# esp8266-lab-kit.net
KiCad netlist of a schematic drawn in EAGLE
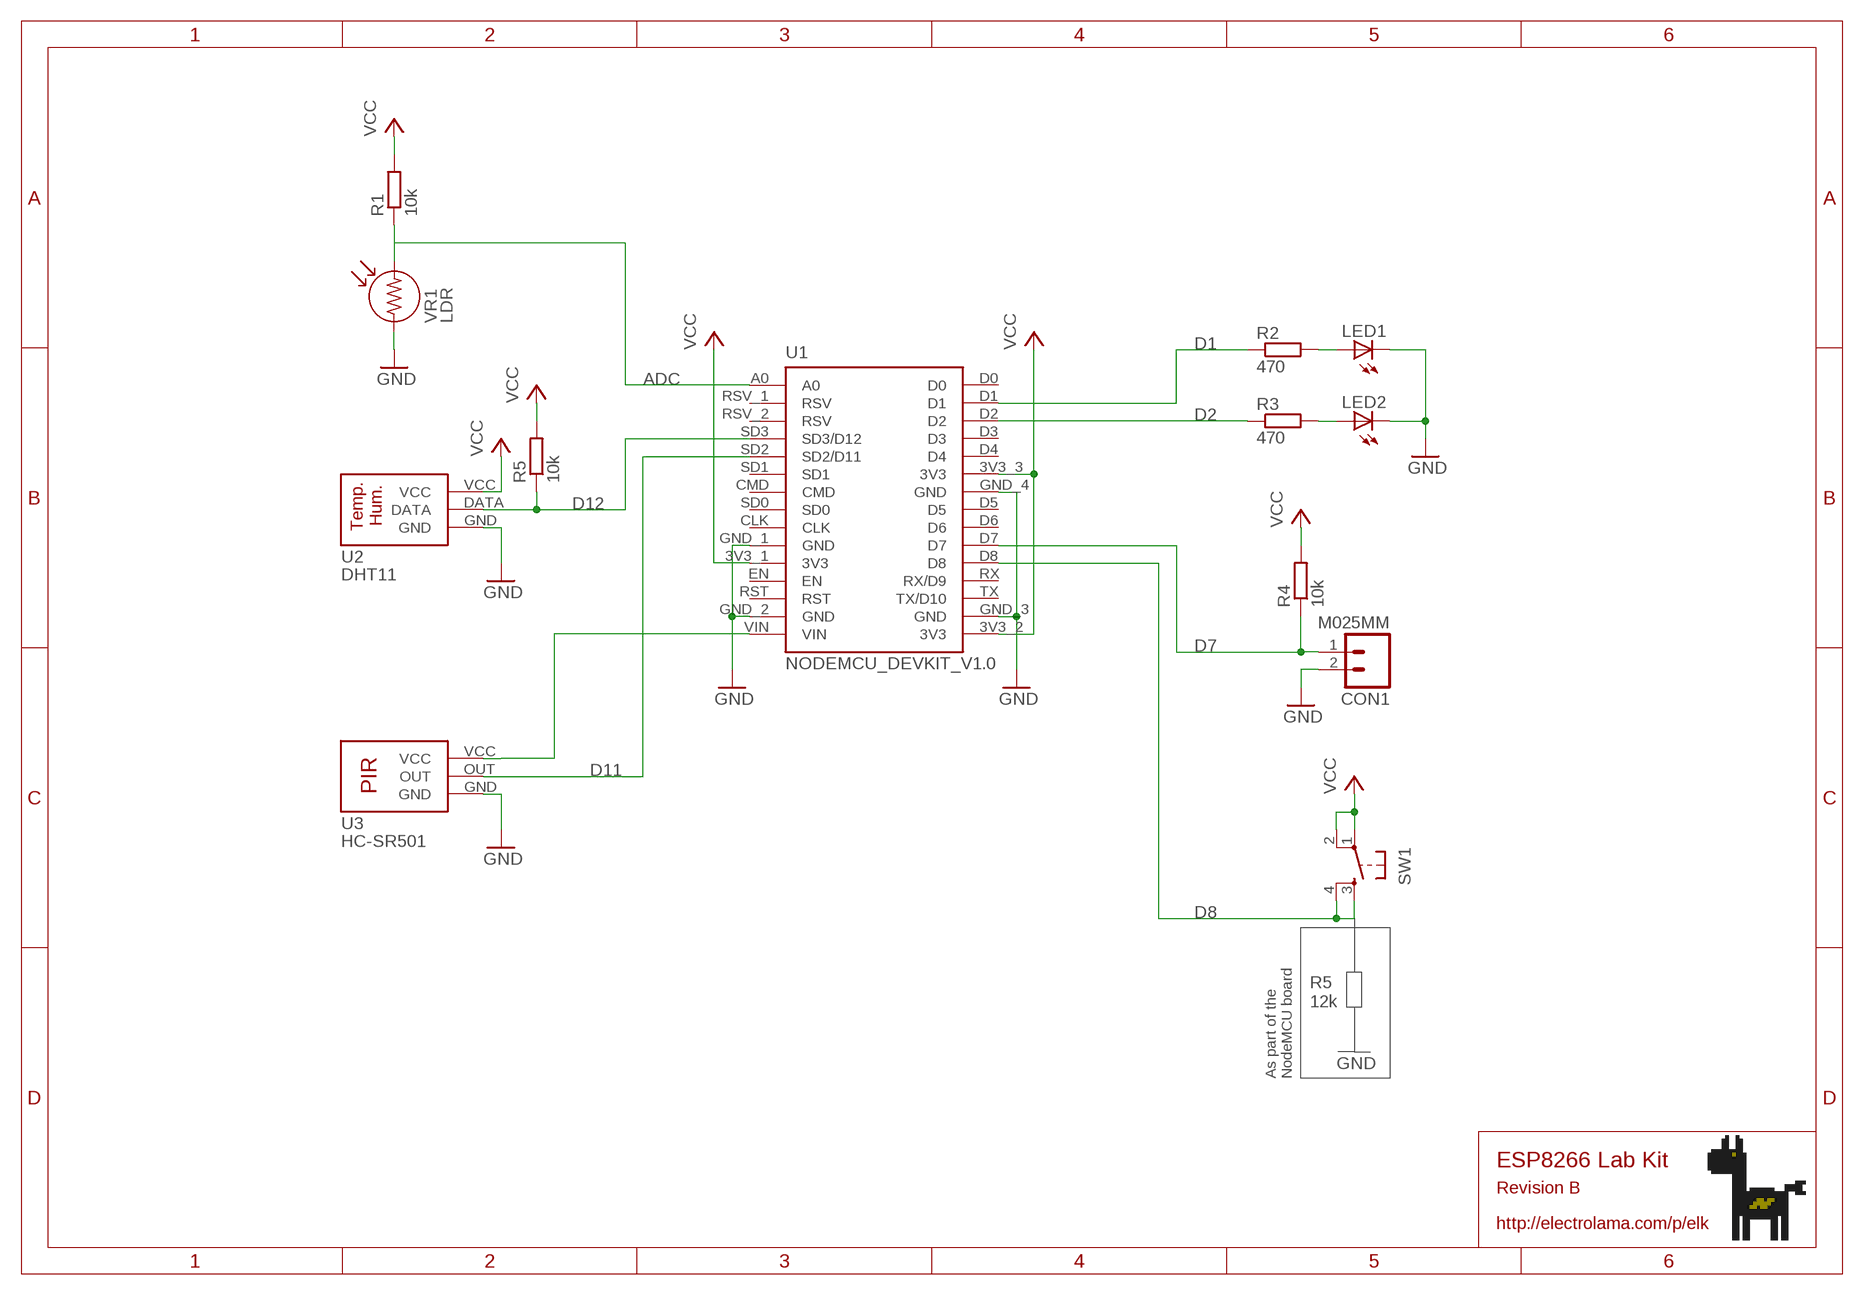
[diagram p0: schematic, sheet 1]

(export (version "E")
  (design (tool "Eeschema 10.0.6"))
  (components
    (comp (ref "CON1")
      (value "M025MM")
      (footprint "eagle-import:SCREWTERMINAL-5MM-2")
      (libsource (lib "eagle-import") (part "M025MM"))
    )
    (comp (ref "LED1")
      (value "LED5MM")
      (footprint "eagle-import:LED5MM")
      (libsource (lib "eagle-import") (part "LED5MM"))
    )
    (comp (ref "LED2")
      (value "LED5MM")
      (footprint "eagle-import:LED5MM")
      (libsource (lib "eagle-import") (part "LED5MM"))
    )
    (comp (ref "R1")
      (value "10k")
      (footprint "eagle-import:RTH025W")
      (libsource (lib "eagle-import") (part "RESISTOR-PTH-0.4"))
    )
    (comp (ref "R2")
      (value "470")
      (footprint "eagle-import:RTH025W")
      (libsource (lib "eagle-import") (part "RESISTOR-PTH-0.4"))
    )
    (comp (ref "R3")
      (value "470")
      (footprint "eagle-import:RTH025W")
      (libsource (lib "eagle-import") (part "RESISTOR-PTH-0.4"))
    )
    (comp (ref "R4")
      (value "10k")
      (footprint "eagle-import:RTH025W")
      (libsource (lib "eagle-import") (part "RESISTOR-PTH-0.4"))
    )
    (comp (ref "R5")
      (value "10k")
      (footprint "eagle-import:RTH025W")
      (libsource (lib "eagle-import") (part "RESISTOR-PTH-0.4"))
    )
    (comp (ref "SW1")
      (value "TAC_SWITCHPTH")
      (footprint "eagle-import:TACTILE-PTH")
      (libsource (lib "eagle-import") (part "TAC_SWITCHPTH"))
    )
    (comp (ref "U1")
      (value "NODEMCU_DEVKIT_V1.0")
      (footprint "eagle-import:NODEMCU_DEVKIT_V1.0")
      (libsource (lib "eagle-import") (part "NODEMCU_DEVKIT_V1.0"))
    )
    (comp (ref "U2")
      (value "DHT11")
      (footprint "eagle-import:DHT11")
      (libsource (lib "eagle-import") (part "DHT11"))
    )
    (comp (ref "U3")
      (value "HC-SR501")
      (footprint "eagle-import:HC-SR501")
      (libsource (lib "eagle-import") (part "HC-SR501"))
    )
    (comp (ref "VR1")
      (value "LDR")
      (footprint "eagle-import:LDR")
      (libsource (lib "eagle-import") (part "LDR"))
    )
  )
  (nets
    (net (code "1") (name "/ADC") (class "Default")
      (node (ref "R1") (pin "1") (pinfunction "1_1") (pintype "passive"))
      (node (ref "U1") (pin "A0") (pinfunction "A0_A0") (pintype "bidirectional"))
      (node (ref "VR1") (pin "2") (pinfunction "2_2") (pintype "passive"))
    )
    (net (code "2") (name "/D1") (class "Default")
      (node (ref "R2") (pin "1") (pinfunction "1_1") (pintype "passive"))
      (node (ref "U1") (pin "D1") (pinfunction "D1_D1") (pintype "bidirectional"))
    )
    (net (code "3") (name "/D2") (class "Default")
      (node (ref "R3") (pin "1") (pinfunction "1_1") (pintype "passive"))
      (node (ref "U1") (pin "D2") (pinfunction "D2_D2") (pintype "bidirectional"))
    )
    (net (code "4") (name "/D7") (class "Default")
      (node (ref "CON1") (pin "1") (pinfunction "1_1") (pintype "passive"))
      (node (ref "R4") (pin "1") (pinfunction "1_1") (pintype "passive"))
      (node (ref "U1") (pin "D7") (pinfunction "D7_D7") (pintype "bidirectional"))
    )
    (net (code "5") (name "/D8") (class "Default")
      (node (ref "SW1") (pin "3") (pinfunction "3_3") (pintype "passive"))
      (node (ref "SW1") (pin "4") (pinfunction "4_4") (pintype "passive"))
      (node (ref "U1") (pin "D8") (pinfunction "D8_D8") (pintype "bidirectional"))
    )
    (net (code "6") (name "/D11") (class "Default")
      (node (ref "U1") (pin "SD2") (pinfunction "SD2/D11_SD2") (pintype "bidirectional"))
      (node (ref "U3") (pin "OUT") (pinfunction "OUT_OUT") (pintype "bidirectional"))
    )
    (net (code "7") (name "/D12") (class "Default")
      (node (ref "R5") (pin "1") (pinfunction "1_1") (pintype "passive"))
      (node (ref "U1") (pin "SD3") (pinfunction "SD3/D12_SD3") (pintype "bidirectional"))
      (node (ref "U2") (pin "DATA") (pinfunction "DATA_DATA") (pintype "bidirectional"))
    )
    (net (code "8") (name "GND") (class "Default")
      (node (ref "CON1") (pin "2") (pinfunction "2_2") (pintype "passive"))
      (node (ref "LED1") (pin "K") (pinfunction "C_K") (pintype "passive"))
      (node (ref "LED2") (pin "K") (pinfunction "C_K") (pintype "passive"))
      (node (ref "U1") (pin "GND_1") (pinfunction "GND_GND_1") (pintype "bidirectional"))
      (node (ref "U1") (pin "GND_2") (pinfunction "GND_GND_2") (pintype "bidirectional"))
      (node (ref "U1") (pin "GND_3") (pinfunction "GND_GND_3") (pintype "bidirectional"))
      (node (ref "U1") (pin "GND_4") (pinfunction "GND_GND_4") (pintype "bidirectional"))
      (node (ref "U2") (pin "GND") (pinfunction "GND_GND") (pintype "power_in"))
      (node (ref "U3") (pin "GND") (pinfunction "GND_GND") (pintype "power_in"))
      (node (ref "VR1") (pin "1") (pinfunction "1_1") (pintype "passive"))
    )
    (net (code "9") (name "Net-(LED1-PadA)") (class "Default")
      (node (ref "LED1") (pin "A") (pinfunction "A_A") (pintype "passive"))
      (node (ref "R2") (pin "2") (pinfunction "2_2") (pintype "passive"))
    )
    (net (code "10") (name "Net-(LED2-PadA)") (class "Default")
      (node (ref "LED2") (pin "A") (pinfunction "A_A") (pintype "passive"))
      (node (ref "R3") (pin "2") (pinfunction "2_2") (pintype "passive"))
    )
    (net (code "11") (name "Net-(U1-PadVIN)") (class "Default")
      (node (ref "U1") (pin "VIN") (pinfunction "VIN_VIN") (pintype "bidirectional"))
      (node (ref "U3") (pin "VCC") (pinfunction "VCC_VCC") (pintype "power_in"))
    )
    (net (code "12") (name "VCC") (class "Default")
      (node (ref "R1") (pin "2") (pinfunction "2_2") (pintype "passive"))
      (node (ref "R4") (pin "2") (pinfunction "2_2") (pintype "passive"))
      (node (ref "R5") (pin "2") (pinfunction "2_2") (pintype "passive"))
      (node (ref "SW1") (pin "1") (pinfunction "1_1") (pintype "passive"))
      (node (ref "SW1") (pin "2") (pinfunction "2_2") (pintype "passive"))
      (node (ref "U1") (pin "3V3_1") (pinfunction "3V3_3V3_1") (pintype "bidirectional"))
      (node (ref "U1") (pin "3V3_2") (pinfunction "3V3_3V3_2") (pintype "bidirectional"))
      (node (ref "U1") (pin "3V3_3") (pinfunction "3V3_3V3_3") (pintype "bidirectional"))
      (node (ref "U2") (pin "VCC") (pinfunction "VCC_VCC") (pintype "power_in"))
    )
    (net (code "13") (name "unconnected-(U1-PadCLK)") (class "Default")
      (node (ref "U1") (pin "CLK") (pinfunction "CLK_CLK") (pintype "bidirectional"))
    )
    (net (code "14") (name "unconnected-(U1-PadCMD)") (class "Default")
      (node (ref "U1") (pin "CMD") (pinfunction "CMD_CMD") (pintype "bidirectional"))
    )
    (net (code "15") (name "unconnected-(U1-PadD0)") (class "Default")
      (node (ref "U1") (pin "D0") (pinfunction "D0_D0") (pintype "bidirectional"))
    )
    (net (code "16") (name "unconnected-(U1-PadD3)") (class "Default")
      (node (ref "U1") (pin "D3") (pinfunction "D3_D3") (pintype "bidirectional"))
    )
    (net (code "17") (name "unconnected-(U1-PadD4)") (class "Default")
      (node (ref "U1") (pin "D4") (pinfunction "D4_D4") (pintype "bidirectional"))
    )
    (net (code "18") (name "unconnected-(U1-PadD5)") (class "Default")
      (node (ref "U1") (pin "D5") (pinfunction "D5_D5") (pintype "bidirectional"))
    )
    (net (code "19") (name "unconnected-(U1-PadD6)") (class "Default")
      (node (ref "U1") (pin "D6") (pinfunction "D6_D6") (pintype "bidirectional"))
    )
    (net (code "20") (name "unconnected-(U1-PadEN)") (class "Default")
      (node (ref "U1") (pin "EN") (pinfunction "EN_EN") (pintype "bidirectional"))
    )
    (net (code "21") (name "unconnected-(U1-PadRST)") (class "Default")
      (node (ref "U1") (pin "RST") (pinfunction "RST_RST") (pintype "bidirectional"))
    )
    (net (code "22") (name "unconnected-(U1-PadSD0)") (class "Default")
      (node (ref "U1") (pin "SD0") (pinfunction "SD0_SD0") (pintype "bidirectional"))
    )
    (net (code "23") (name "unconnected-(U1-PadSD1)") (class "Default")
      (node (ref "U1") (pin "SD1") (pinfunction "SD1_SD1") (pintype "bidirectional"))
    )
    (net (code "24") (name "unconnected-(U1-RSV-PadRSV_1)") (class "Default")
      (node (ref "U1") (pin "RSV_1") (pinfunction "RSV_RSV_1") (pintype "bidirectional"))
    )
    (net (code "25") (name "unconnected-(U1-RSV-PadRSV_2)") (class "Default")
      (node (ref "U1") (pin "RSV_2") (pinfunction "RSV_RSV_2") (pintype "bidirectional"))
    )
    (net (code "26") (name "unconnected-(U1-RX{slash}D9-PadRX)") (class "Default")
      (node (ref "U1") (pin "RX") (pinfunction "RX/D9_RX") (pintype "bidirectional"))
    )
    (net (code "27") (name "unconnected-(U1-TX{slash}D10-PadTX)") (class "Default")
      (node (ref "U1") (pin "TX") (pinfunction "TX/D10_TX") (pintype "bidirectional"))
    )
  )
)
